# rev02_13.net
KiCad netlist of a schematic drawn in Altium Designer
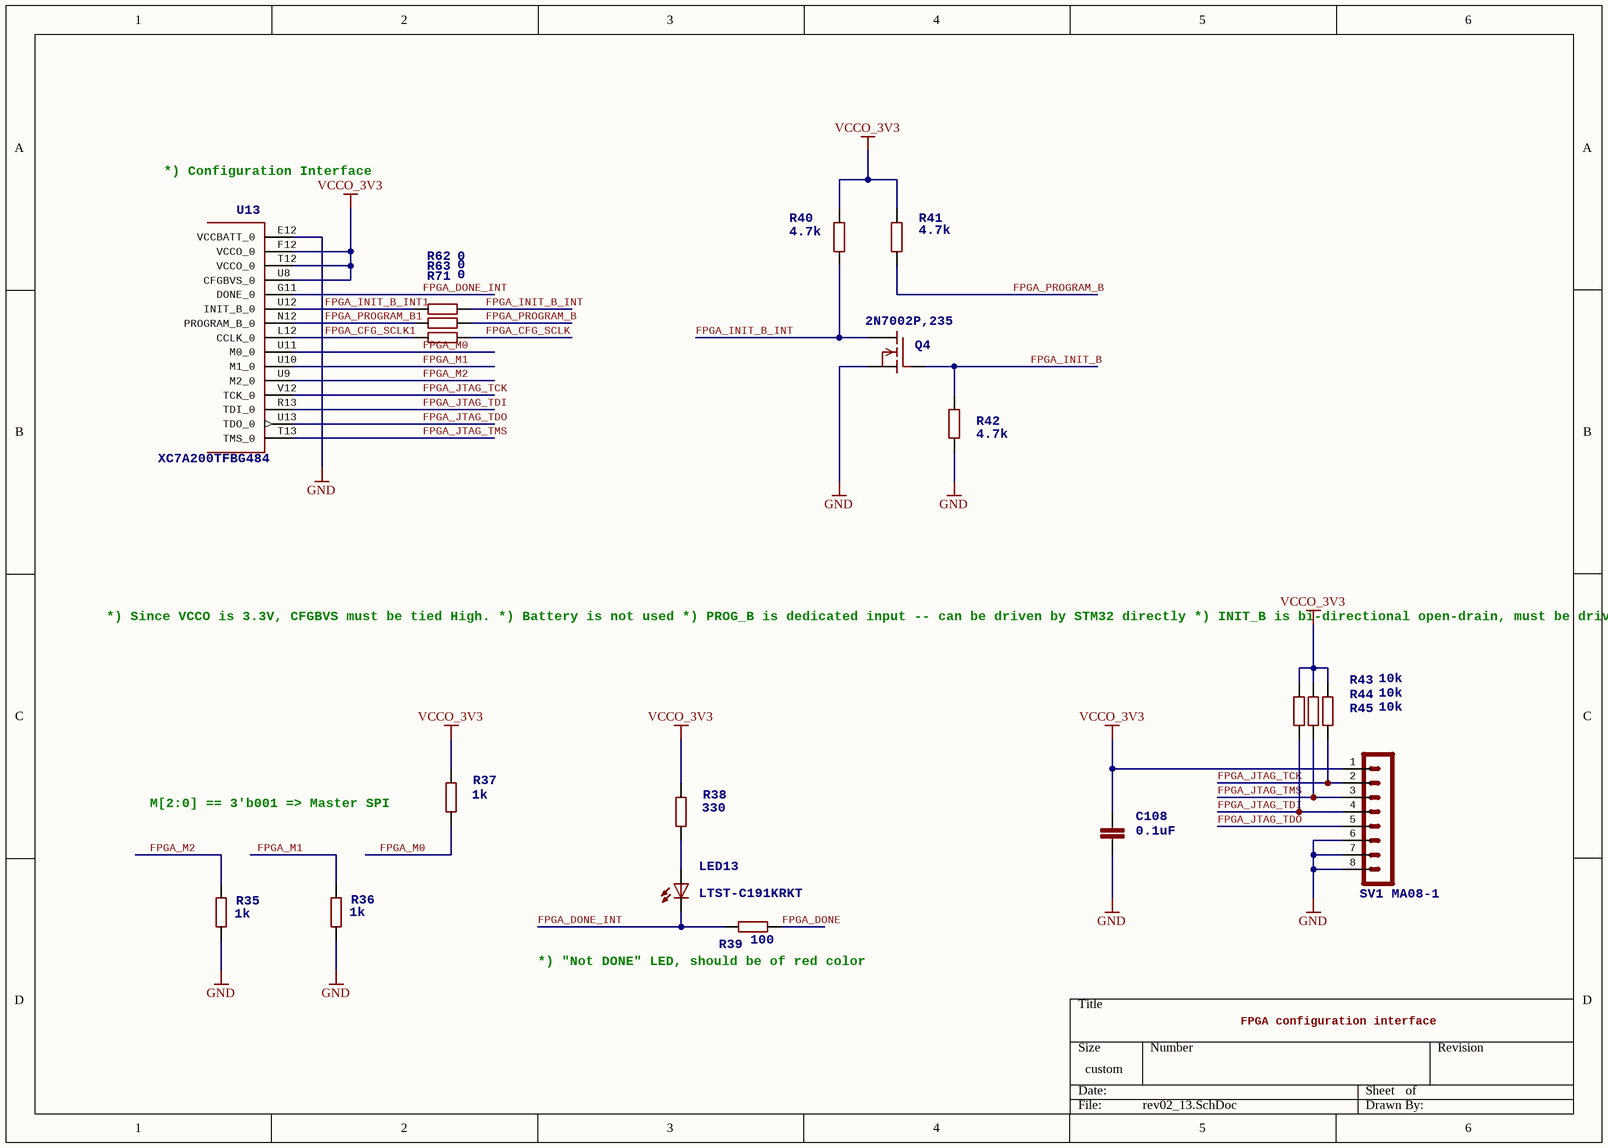
[diagram p0: rev02_13.SchDoc]

(export (version "E")
  (design (tool "Eeschema 10.0.6"))
  (components
    (comp (ref "C108")
      (value "0.1uF")
      (footprint "C_0402")
      (description "0402 CAPACITOR")
      (fields (field (name "TOLERANCE") "10%") (field (name ">NAME") "C108"))
      (libsource (lib "resistor") (part "C-EUC0402"))
    )
    (comp (ref "LED13")
      (value "LTST-C191KRKT")
      (footprint "VD_0603")
      (description "RED LED")
      (libsource (lib "rev02_1") (part "LEDCHIP-LED0603"))
    )
    (comp (ref "Q4")
      (value "2N7002P,235")
      (footprint "SOT-23")
      (description "OnSemi FET")
      (fields (field (name ">NAME") "Q4"))
      (libsource (lib "transistors_gaui") (part "2N7002"))
    )
    (comp (ref "R35")
      (value "1k")
      (footprint "R_0402")
      (description "0402 Resistor 5%")
      (fields (field (name "TOLERANCE") "5%") (field (name ">NAME") "R35"))
      (libsource (lib "resistor") (part "R-EU_R0402"))
    )
    (comp (ref "R36")
      (value "1k")
      (footprint "R_0402")
      (description "0402 Resistor 5%")
      (fields (field (name "TOLERANCE") "5%") (field (name ">NAME") "R36"))
      (libsource (lib "resistor") (part "R-EU_R0402"))
    )
    (comp (ref "R37")
      (value "1k")
      (footprint "R_0402")
      (description "0402 Resistor 5%")
      (libsource (lib "resistor") (part "R-EU_R0402"))
    )
    (comp (ref "R38")
      (value "330")
      (footprint "R_0402")
      (description "0402 Resistor 5%")
      (libsource (lib "resistor") (part "R-EU_R0402"))
    )
    (comp (ref "R39")
      (value "100")
      (footprint "R_0402")
      (description "0402 Resistor 5%")
      (fields (field (name "TOLERANCE") "5%") (field (name ">NAME") "R39"))
      (libsource (lib "resistor") (part "R-EU_R0402"))
    )
    (comp (ref "R40")
      (value "4.7k")
      (footprint "R_0402")
      (description "0402 Resistor 5%")
      (libsource (lib "resistor") (part "R-EU_R0402"))
    )
    (comp (ref "R41")
      (value "4.7k")
      (footprint "R_0402")
      (description "0402 Resistor 5%")
      (libsource (lib "resistor") (part "R-EU_R0402"))
    )
    (comp (ref "R42")
      (value "4.7k")
      (footprint "R_0402")
      (description "0402 Resistor 5%")
      (libsource (lib "resistor") (part "R-EU_R0402"))
    )
    (comp (ref "R43")
      (value "10k")
      (footprint "R_0402")
      (description "0402 Resistor 5%")
      (libsource (lib "resistor") (part "R-EU_R0402"))
    )
    (comp (ref "R44")
      (value "10k")
      (footprint "R_0402")
      (description "0402 Resistor 5%")
      (libsource (lib "resistor") (part "R-EU_R0402"))
    )
    (comp (ref "R45")
      (value "10k")
      (footprint "R_0402")
      (description "0402 Resistor 5%")
      (libsource (lib "resistor") (part "R-EU_R0402"))
    )
    (comp (ref "R62")
      (value "0")
      (footprint "R_0402")
      (description "0402 Resistor 5%")
      (libsource (lib "resistor") (part "R-EU_R0603"))
    )
    (comp (ref "R63")
      (value "0")
      (footprint "R_0402")
      (description "0402 Resistor 5%")
      (libsource (lib "resistor") (part "R-EU_R0603"))
    )
    (comp (ref "R71")
      (value "0")
      (footprint "R_0402")
      (description "0402 Resistor 5%")
      (libsource (lib "resistor") (part "R-EU_R0603"))
    )
    (comp (ref "SV1")
      (value "MA08-1")
      (footprint "PLS-8")
      (description "PIN HEADER 0.1\"")
      (libsource (lib "con-lstb") (part "MA08-1"))
    )
    (comp (ref "U13")
      (value "XC7A200TFBG484")
      (footprint "BGA484C100P22X22_2300X2300X254")
      (description "Xilinx FPGA: XC7A200TFBG484")
      (fields
        (field (name "MFR") "Xilinx")
        (field (name "MPN") "XC7A200T-1FBG484C")
        (field (name ">NAME") "U13")
        (field (name ">VALUE") "XC7A200TFBG484")
      )
      (libsource (lib "Xilinx_XC7A200TFBG484") (part "XC7A200TFBG484"))
    )
  )
  (nets
    (net (code "1") (name "/FPGA_CFG_SCLK") (class "Default")
      (node (ref "R71") (pin "1") (pinfunction "1_1") (pintype "passive"))
    )
    (net (code "2") (name "/FPGA_CFG_SCLK1") (class "Default")
      (node (ref "R71") (pin "2") (pinfunction "2_2") (pintype "passive"))
      (node (ref "U13") (pin "L12") (pinfunction "CCLK_0_L12") (pintype "passive"))
    )
    (net (code "3") (name "/FPGA_DONE") (class "Default")
      (node (ref "R39") (pin "1") (pinfunction "1_1") (pintype "passive"))
    )
    (net (code "4") (name "/FPGA_DONE_INT") (class "Default")
      (node (ref "LED13") (pin "2") (pinfunction "C_2") (pintype "passive"))
      (node (ref "R39") (pin "2") (pinfunction "2_2") (pintype "passive"))
      (node (ref "U13") (pin "G11") (pinfunction "DONE_0_G11") (pintype "passive"))
    )
    (net (code "5") (name "/FPGA_INIT_B") (class "Default")
      (node (ref "Q4") (pin "1") (pinfunction "G_1") (pintype "passive"))
      (node (ref "R42") (pin "2") (pinfunction "2_2") (pintype "passive"))
    )
    (net (code "6") (name "/FPGA_INIT_B_INT") (class "Default")
      (node (ref "Q4") (pin "3") (pinfunction "D_3") (pintype "passive"))
      (node (ref "R40") (pin "1") (pinfunction "1_1") (pintype "passive"))
      (node (ref "R62") (pin "1") (pinfunction "1_1") (pintype "passive"))
    )
    (net (code "7") (name "/FPGA_INIT_B_INT1") (class "Default")
      (node (ref "R62") (pin "2") (pinfunction "2_2") (pintype "passive"))
      (node (ref "U13") (pin "U12") (pinfunction "INIT_B_0_U12") (pintype "open_collector"))
    )
    (net (code "8") (name "/FPGA_JTAG_TCK") (class "Default")
      (node (ref "R45") (pin "1") (pinfunction "1_1") (pintype "passive"))
      (node (ref "SV1") (pin "2") (pinfunction "2_2") (pintype "passive"))
      (node (ref "U13") (pin "V12") (pinfunction "TCK_0_V12") (pintype "passive"))
    )
    (net (code "9") (name "/FPGA_JTAG_TDI") (class "Default")
      (node (ref "R43") (pin "1") (pinfunction "1_1") (pintype "passive"))
      (node (ref "SV1") (pin "4") (pinfunction "4_4") (pintype "passive"))
      (node (ref "U13") (pin "R13") (pinfunction "TDI_0_R13") (pintype "passive"))
    )
    (net (code "10") (name "/FPGA_JTAG_TDO") (class "Default")
      (node (ref "SV1") (pin "5") (pinfunction "5_5") (pintype "passive"))
      (node (ref "U13") (pin "U13") (pinfunction "TDO_0_U13") (pintype "output"))
    )
    (net (code "11") (name "/FPGA_JTAG_TMS") (class "Default")
      (node (ref "R44") (pin "1") (pinfunction "1_1") (pintype "passive"))
      (node (ref "SV1") (pin "3") (pinfunction "3_3") (pintype "passive"))
      (node (ref "U13") (pin "T13") (pinfunction "TMS_0_T13") (pintype "passive"))
    )
    (net (code "12") (name "/FPGA_M0") (class "Default")
      (node (ref "R37") (pin "1") (pinfunction "1_1") (pintype "passive"))
      (node (ref "U13") (pin "U11") (pinfunction "M0_0_U11") (pintype "passive"))
    )
    (net (code "13") (name "/FPGA_M1") (class "Default")
      (node (ref "R36") (pin "2") (pinfunction "2_2") (pintype "passive"))
      (node (ref "U13") (pin "U10") (pinfunction "M1_0_U10") (pintype "passive"))
    )
    (net (code "14") (name "/FPGA_M2") (class "Default")
      (node (ref "R35") (pin "2") (pinfunction "2_2") (pintype "passive"))
      (node (ref "U13") (pin "U9") (pinfunction "M2_0_U9") (pintype "passive"))
    )
    (net (code "15") (name "/FPGA_PROGRAM_B") (class "Default")
      (node (ref "R41") (pin "1") (pinfunction "1_1") (pintype "passive"))
      (node (ref "R63") (pin "1") (pinfunction "1_1") (pintype "passive"))
    )
    (net (code "16") (name "/FPGA_PROGRAM_B1") (class "Default")
      (node (ref "R63") (pin "2") (pinfunction "2_2") (pintype "passive"))
      (node (ref "U13") (pin "N12") (pinfunction "PROGRAM_B_0_N12") (pintype "passive"))
    )
    (net (code "17") (name "GND") (class "Default")
      (node (ref "C108") (pin "2") (pinfunction "2_2") (pintype "passive"))
      (node (ref "Q4") (pin "2") (pinfunction "S_2") (pintype "passive"))
      (node (ref "R35") (pin "1") (pinfunction "1_1") (pintype "passive"))
      (node (ref "R36") (pin "1") (pinfunction "1_1") (pintype "passive"))
      (node (ref "R42") (pin "1") (pinfunction "1_1") (pintype "passive"))
      (node (ref "SV1") (pin "6") (pinfunction "6_6") (pintype "passive"))
      (node (ref "SV1") (pin "7") (pinfunction "7_7") (pintype "passive"))
      (node (ref "SV1") (pin "8") (pinfunction "8_8") (pintype "passive"))
      (node (ref "U13") (pin "E12") (pinfunction "VCCBATT_0_E12") (pintype "passive"))
    )
    (net (code "18") (name "Net-(LED13-A)") (class "Default")
      (node (ref "LED13") (pin "1") (pinfunction "A_1") (pintype "passive"))
      (node (ref "R38") (pin "1") (pinfunction "1_1") (pintype "passive"))
    )
    (net (code "19") (name "VCCO_3V3") (class "Default")
      (node (ref "C108") (pin "1") (pinfunction "1_1") (pintype "passive"))
      (node (ref "R37") (pin "2") (pinfunction "2_2") (pintype "passive"))
      (node (ref "R38") (pin "2") (pinfunction "2_2") (pintype "passive"))
      (node (ref "R40") (pin "2") (pinfunction "2_2") (pintype "passive"))
      (node (ref "R41") (pin "2") (pinfunction "2_2") (pintype "passive"))
      (node (ref "R43") (pin "2") (pinfunction "2_2") (pintype "passive"))
      (node (ref "R44") (pin "2") (pinfunction "2_2") (pintype "passive"))
      (node (ref "R45") (pin "2") (pinfunction "2_2") (pintype "passive"))
      (node (ref "SV1") (pin "1") (pinfunction "1_1") (pintype "passive"))
      (node (ref "U13") (pin "F12") (pinfunction "VCCO_0_F12") (pintype "passive"))
      (node (ref "U13") (pin "T12") (pinfunction "VCCO_0_T12") (pintype "passive"))
      (node (ref "U13") (pin "U8") (pinfunction "CFGBVS_0_U8") (pintype "passive"))
    )
  )
)
